# Serial.net
KiCad netlist of a schematic drawn in Altium Designer
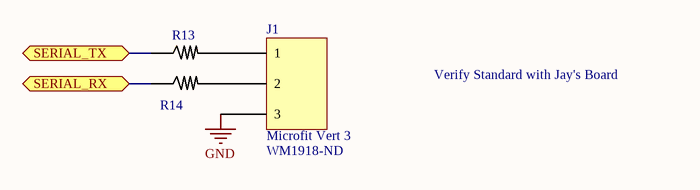
[diagram p0: Serial.SchDoc]

(export (version "E")
  (design (tool "Eeschema 10.0.6"))
  (components
    (comp (ref "J1")
      (value "Microfit Vert 3")
      (footprint "MICRO-FIT 3 POS VERT THROUGH HOLE")
      (fields (field (name "SUPPLIER PART NUMBER 1") "WM1918-ND"))
      (libsource (lib "CornellBajaLibrary") (part "Micro-fit 3 Pos Vertical Through Hole"))
    )
    (comp (ref "R13")
      (value "0603 Res")
      (footprint "0603/1608 SMD Resistor")
      (description "220 Ohm Res")
      (libsource (lib "BajaIntegrated") (part "0603 Res"))
    )
    (comp (ref "R14")
      (value "0603 Res")
      (footprint "0603/1608 SMD Resistor")
      (description "220 Ohm Res")
      (libsource (lib "BajaIntegrated") (part "0603 Res"))
    )
  )
  (nets
    (net (code "1") (name "/SERIAL_RX") (class "Default")
      (node (ref "R14") (pin "1") (pinfunction "1_1") (pintype "passive"))
    )
    (net (code "2") (name "/SERIAL_TX") (class "Default")
      (node (ref "R13") (pin "1") (pinfunction "1_1") (pintype "passive"))
    )
    (net (code "3") (name "GND") (class "Default")
      (node (ref "J1") (pin "3") (pinfunction "3_3") (pintype "passive"))
    )
    (net (code "4") (name "Net-(J1-Pad1)") (class "Default")
      (node (ref "J1") (pin "1") (pinfunction "1_1") (pintype "passive"))
      (node (ref "R13") (pin "2") (pinfunction "2_2") (pintype "passive"))
    )
    (net (code "5") (name "Net-(J1-Pad2)") (class "Default")
      (node (ref "J1") (pin "2") (pinfunction "2_2") (pintype "passive"))
      (node (ref "R14") (pin "2") (pinfunction "2_2") (pintype "passive"))
    )
  )
)
